# 3DG.net
KiCad netlist of a schematic drawn in EAGLE
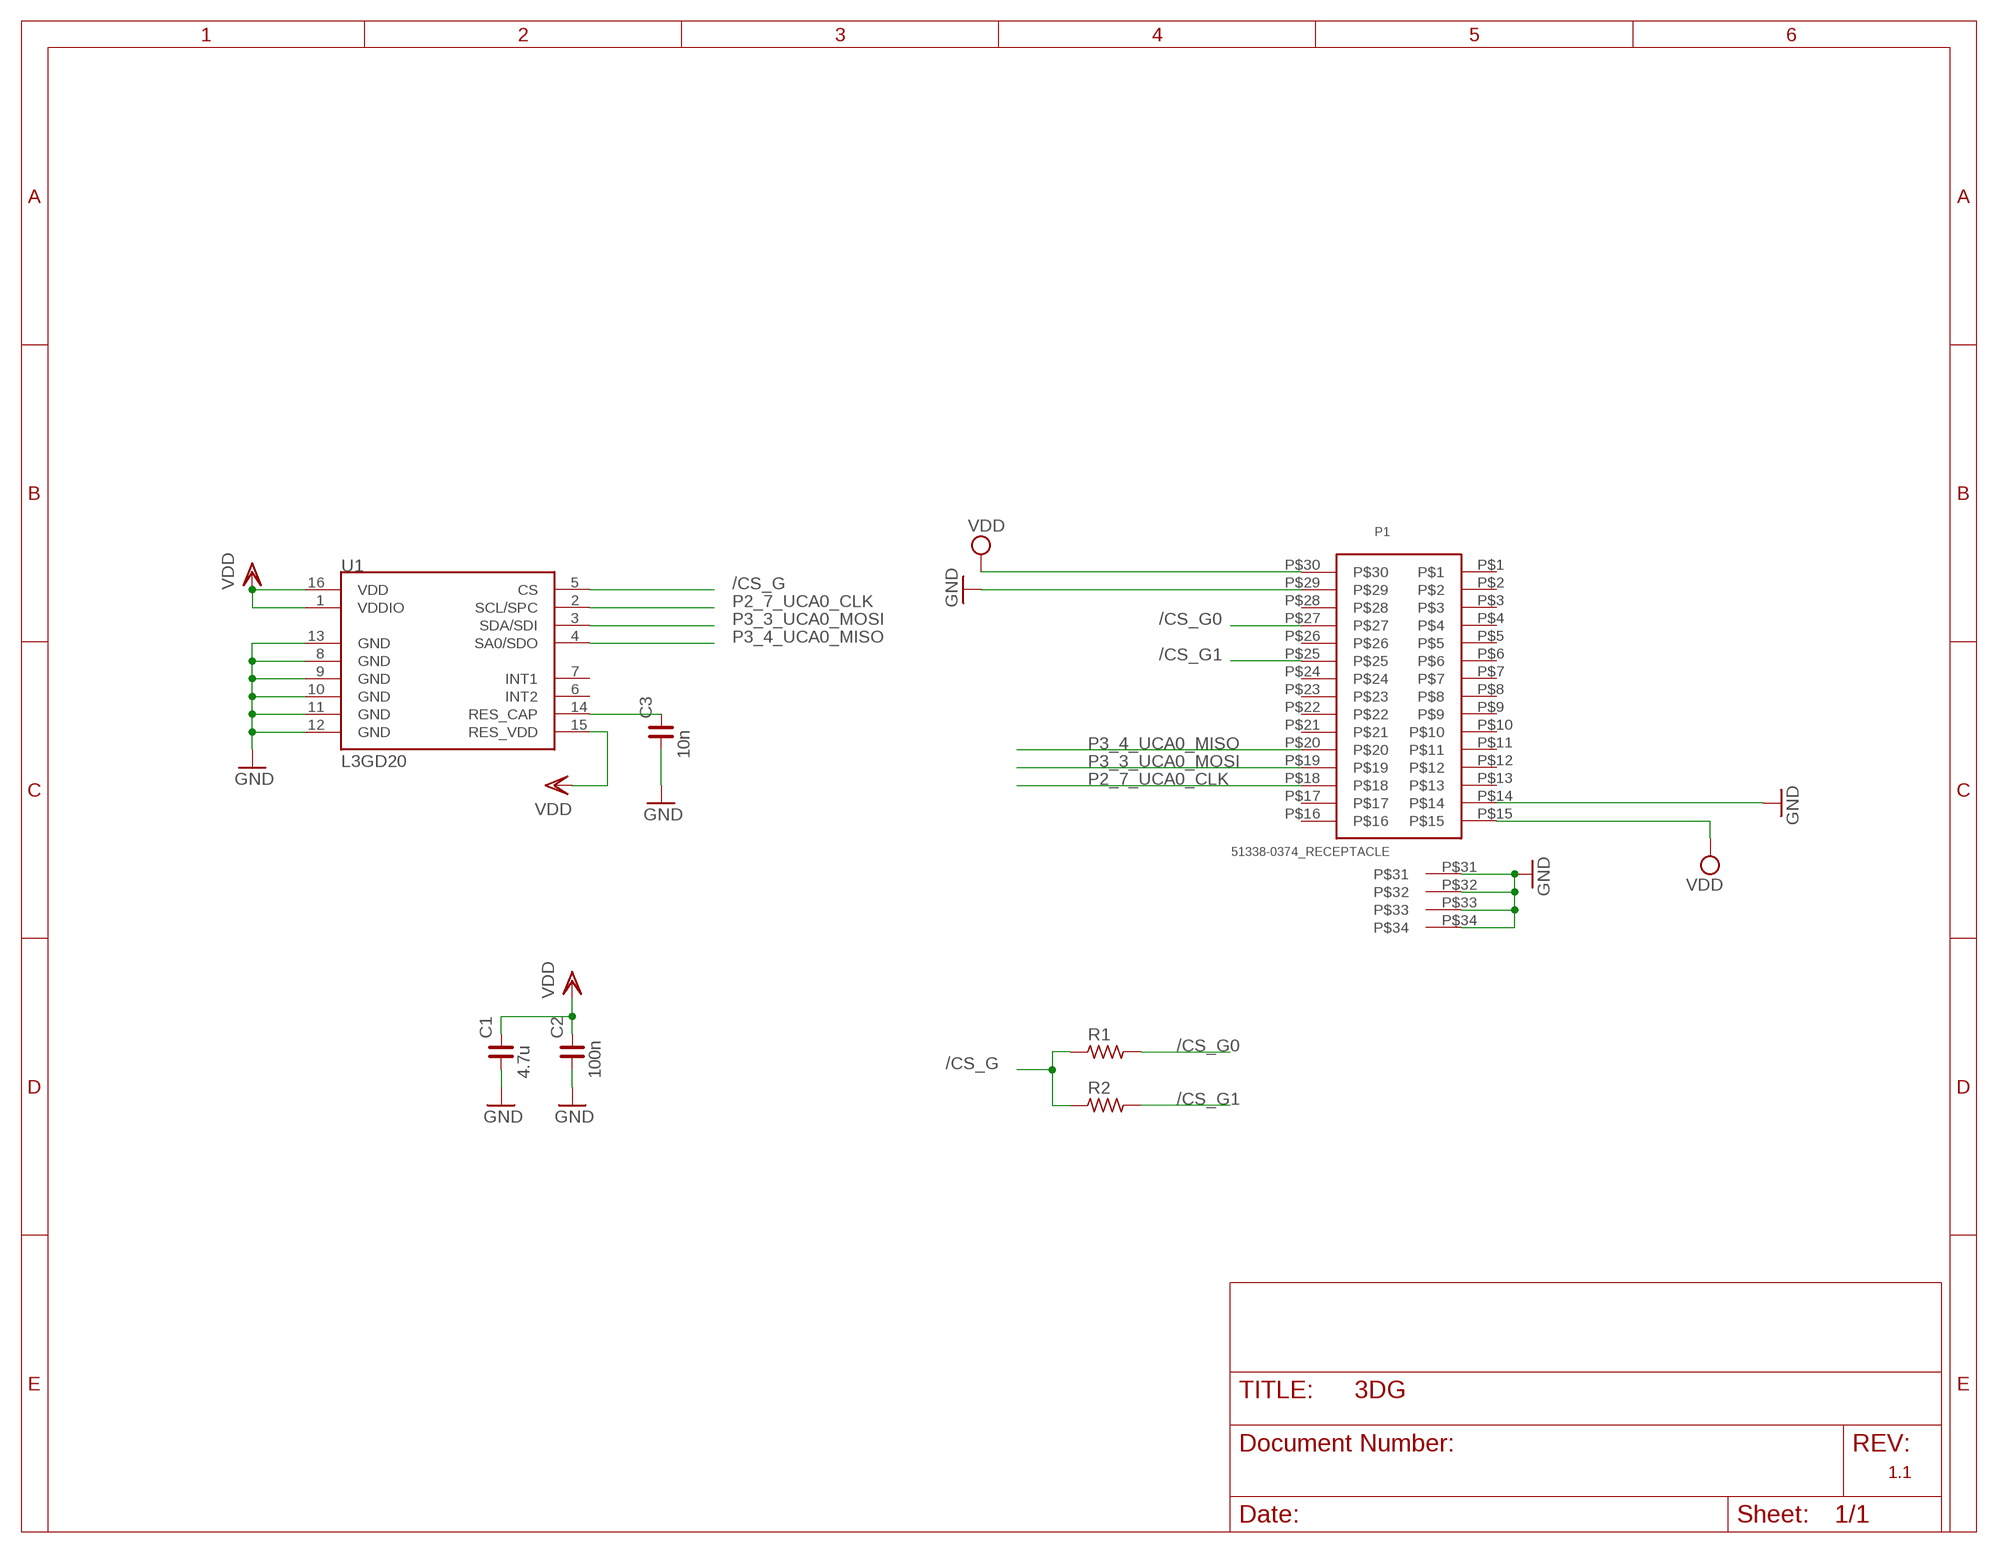
[diagram p0: schematic, sheet 1]

(export (version "E")
  (design (tool "Eeschema 10.0.6"))
  (components
    (comp (ref "C1")
      (value "4.7u")
      (footprint "eagle-import:C0402")
      (libsource (lib "eagle-import") (part "C_0402"))
    )
    (comp (ref "C2")
      (value "100n")
      (footprint "eagle-import:C0402")
      (libsource (lib "eagle-import") (part "C_0402"))
    )
    (comp (ref "C3")
      (value "10n")
      (footprint "eagle-import:C0402")
      (libsource (lib "eagle-import") (part "C_0402"))
    )
    (comp (ref "P1")
      (value "51338-0374_RECEPTACLE")
      (footprint "eagle-import:51338-0374_RECEPTACLE")
      (libsource (lib "eagle-import") (part "51338-0374_RECEPTACLE"))
    )
    (comp (ref "R1")
      (value "R_0402")
      (footprint "eagle-import:R0402")
      (libsource (lib "eagle-import") (part "R_0402"))
    )
    (comp (ref "R2")
      (value "R_0402")
      (footprint "eagle-import:R0402")
      (libsource (lib "eagle-import") (part "R_0402"))
    )
    (comp (ref "U1")
      (value "L3GD20")
      (footprint "eagle-import:LGA16-4X4")
      (libsource (lib "eagle-import") (part "L3GD20"))
    )
  )
  (nets
    (net (code "1") (name "/P2_7_UCA0_CLK") (class "Default")
      (node (ref "P1") (pin "P$18") (pinfunction "P$18_P$18") (pintype "bidirectional"))
      (node (ref "U1") (pin "2") (pinfunction "SCL/SPC_2") (pintype "bidirectional"))
    )
    (net (code "2") (name "/P3_3_UCA0_MOSI") (class "Default")
      (node (ref "P1") (pin "P$19") (pinfunction "P$19_P$19") (pintype "bidirectional"))
      (node (ref "U1") (pin "3") (pinfunction "SDA/SDI_3") (pintype "bidirectional"))
    )
    (net (code "3") (name "/P3_4_UCA0_MISO") (class "Default")
      (node (ref "P1") (pin "P$20") (pinfunction "P$20_P$20") (pintype "bidirectional"))
      (node (ref "U1") (pin "4") (pinfunction "SA0/SDO_4") (pintype "bidirectional"))
    )
    (net (code "4") (name "/{slash}CS_G") (class "Default")
      (node (ref "R1") (pin "1") (pinfunction "1_1") (pintype "passive"))
      (node (ref "R2") (pin "1") (pinfunction "1_1") (pintype "passive"))
      (node (ref "U1") (pin "5") (pinfunction "CS_5") (pintype "bidirectional"))
    )
    (net (code "5") (name "/{slash}CS_G0") (class "Default")
      (node (ref "P1") (pin "P$27") (pinfunction "P$27_P$27") (pintype "bidirectional"))
      (node (ref "R1") (pin "2") (pinfunction "2_2") (pintype "passive"))
    )
    (net (code "6") (name "/{slash}CS_G1") (class "Default")
      (node (ref "P1") (pin "P$25") (pinfunction "P$25_P$25") (pintype "bidirectional"))
      (node (ref "R2") (pin "2") (pinfunction "2_2") (pintype "passive"))
    )
    (net (code "7") (name "GND") (class "Default")
      (node (ref "C1") (pin "1") (pinfunction "1_1") (pintype "passive"))
      (node (ref "C2") (pin "1") (pinfunction "1_1") (pintype "passive"))
      (node (ref "C3") (pin "1") (pinfunction "1_1") (pintype "passive"))
      (node (ref "P1") (pin "P$14") (pinfunction "P$14_P$14") (pintype "bidirectional"))
      (node (ref "P1") (pin "P$29") (pinfunction "P$29_P$29") (pintype "bidirectional"))
      (node (ref "P1") (pin "P$31") (pinfunction "P$31_P$31") (pintype "bidirectional"))
      (node (ref "P1") (pin "P$32") (pinfunction "P$32_P$32") (pintype "bidirectional"))
      (node (ref "P1") (pin "P$33") (pinfunction "P$33_P$33") (pintype "bidirectional"))
      (node (ref "P1") (pin "P$34") (pinfunction "P$34_P$34") (pintype "bidirectional"))
      (node (ref "U1") (pin "10") (pinfunction "GND_10") (pintype "bidirectional"))
      (node (ref "U1") (pin "11") (pinfunction "GND_11") (pintype "bidirectional"))
      (node (ref "U1") (pin "12") (pinfunction "GND_12") (pintype "bidirectional"))
      (node (ref "U1") (pin "13") (pinfunction "GND_13") (pintype "bidirectional"))
      (node (ref "U1") (pin "8") (pinfunction "GND_8") (pintype "bidirectional"))
      (node (ref "U1") (pin "9") (pinfunction "GND_9") (pintype "bidirectional"))
    )
    (net (code "8") (name "Net-(U1-RES_CAP)") (class "Default")
      (node (ref "C3") (pin "2") (pinfunction "2_2") (pintype "passive"))
      (node (ref "U1") (pin "14") (pinfunction "RES_CAP_14") (pintype "bidirectional"))
    )
    (net (code "9") (name "VDD") (class "Default")
      (node (ref "C1") (pin "2") (pinfunction "2_2") (pintype "passive"))
      (node (ref "C2") (pin "2") (pinfunction "2_2") (pintype "passive"))
      (node (ref "P1") (pin "P$15") (pinfunction "P$15_P$15") (pintype "bidirectional"))
      (node (ref "P1") (pin "P$30") (pinfunction "P$30_P$30") (pintype "bidirectional"))
      (node (ref "U1") (pin "1") (pinfunction "VDDIO_1") (pintype "bidirectional"))
      (node (ref "U1") (pin "15") (pinfunction "RES_VDD_15") (pintype "bidirectional"))
      (node (ref "U1") (pin "16") (pinfunction "VDD_16") (pintype "bidirectional"))
    )
    (net (code "10") (name "unconnected-(P1-PadP$1)") (class "Default")
      (node (ref "P1") (pin "P$1") (pinfunction "P$1_P$1") (pintype "bidirectional"))
    )
    (net (code "11") (name "unconnected-(P1-PadP$2)") (class "Default")
      (node (ref "P1") (pin "P$2") (pinfunction "P$2_P$2") (pintype "bidirectional"))
    )
    (net (code "12") (name "unconnected-(P1-PadP$3)") (class "Default")
      (node (ref "P1") (pin "P$3") (pinfunction "P$3_P$3") (pintype "bidirectional"))
    )
    (net (code "13") (name "unconnected-(P1-PadP$4)") (class "Default")
      (node (ref "P1") (pin "P$4") (pinfunction "P$4_P$4") (pintype "bidirectional"))
    )
    (net (code "14") (name "unconnected-(P1-PadP$5)") (class "Default")
      (node (ref "P1") (pin "P$5") (pinfunction "P$5_P$5") (pintype "bidirectional"))
    )
    (net (code "15") (name "unconnected-(P1-PadP$6)") (class "Default")
      (node (ref "P1") (pin "P$6") (pinfunction "P$6_P$6") (pintype "bidirectional"))
    )
    (net (code "16") (name "unconnected-(P1-PadP$7)") (class "Default")
      (node (ref "P1") (pin "P$7") (pinfunction "P$7_P$7") (pintype "bidirectional"))
    )
    (net (code "17") (name "unconnected-(P1-PadP$8)") (class "Default")
      (node (ref "P1") (pin "P$8") (pinfunction "P$8_P$8") (pintype "bidirectional"))
    )
    (net (code "18") (name "unconnected-(P1-PadP$9)") (class "Default")
      (node (ref "P1") (pin "P$9") (pinfunction "P$9_P$9") (pintype "bidirectional"))
    )
    (net (code "19") (name "unconnected-(P1-PadP$10)") (class "Default")
      (node (ref "P1") (pin "P$10") (pinfunction "P$10_P$10") (pintype "bidirectional"))
    )
    (net (code "20") (name "unconnected-(P1-PadP$11)") (class "Default")
      (node (ref "P1") (pin "P$11") (pinfunction "P$11_P$11") (pintype "bidirectional"))
    )
    (net (code "21") (name "unconnected-(P1-PadP$12)") (class "Default")
      (node (ref "P1") (pin "P$12") (pinfunction "P$12_P$12") (pintype "bidirectional"))
    )
    (net (code "22") (name "unconnected-(P1-PadP$13)") (class "Default")
      (node (ref "P1") (pin "P$13") (pinfunction "P$13_P$13") (pintype "bidirectional"))
    )
    (net (code "23") (name "unconnected-(P1-PadP$16)") (class "Default")
      (node (ref "P1") (pin "P$16") (pinfunction "P$16_P$16") (pintype "bidirectional"))
    )
    (net (code "24") (name "unconnected-(P1-PadP$17)") (class "Default")
      (node (ref "P1") (pin "P$17") (pinfunction "P$17_P$17") (pintype "bidirectional"))
    )
    (net (code "25") (name "unconnected-(P1-PadP$21)") (class "Default")
      (node (ref "P1") (pin "P$21") (pinfunction "P$21_P$21") (pintype "bidirectional"))
    )
    (net (code "26") (name "unconnected-(P1-PadP$22)") (class "Default")
      (node (ref "P1") (pin "P$22") (pinfunction "P$22_P$22") (pintype "bidirectional"))
    )
    (net (code "27") (name "unconnected-(P1-PadP$23)") (class "Default")
      (node (ref "P1") (pin "P$23") (pinfunction "P$23_P$23") (pintype "bidirectional"))
    )
    (net (code "28") (name "unconnected-(P1-PadP$24)") (class "Default")
      (node (ref "P1") (pin "P$24") (pinfunction "P$24_P$24") (pintype "bidirectional"))
    )
    (net (code "29") (name "unconnected-(P1-PadP$26)") (class "Default")
      (node (ref "P1") (pin "P$26") (pinfunction "P$26_P$26") (pintype "bidirectional"))
    )
    (net (code "30") (name "unconnected-(P1-PadP$28)") (class "Default")
      (node (ref "P1") (pin "P$28") (pinfunction "P$28_P$28") (pintype "bidirectional"))
    )
    (net (code "31") (name "unconnected-(U1-INT1-Pad7)") (class "Default")
      (node (ref "U1") (pin "7") (pinfunction "INT1_7") (pintype "bidirectional"))
    )
    (net (code "32") (name "unconnected-(U1-INT2-Pad6)") (class "Default")
      (node (ref "U1") (pin "6") (pinfunction "INT2_6") (pintype "bidirectional"))
    )
  )
)
